# design.net
KiCad netlist of a schematic drawn in Altium Designer
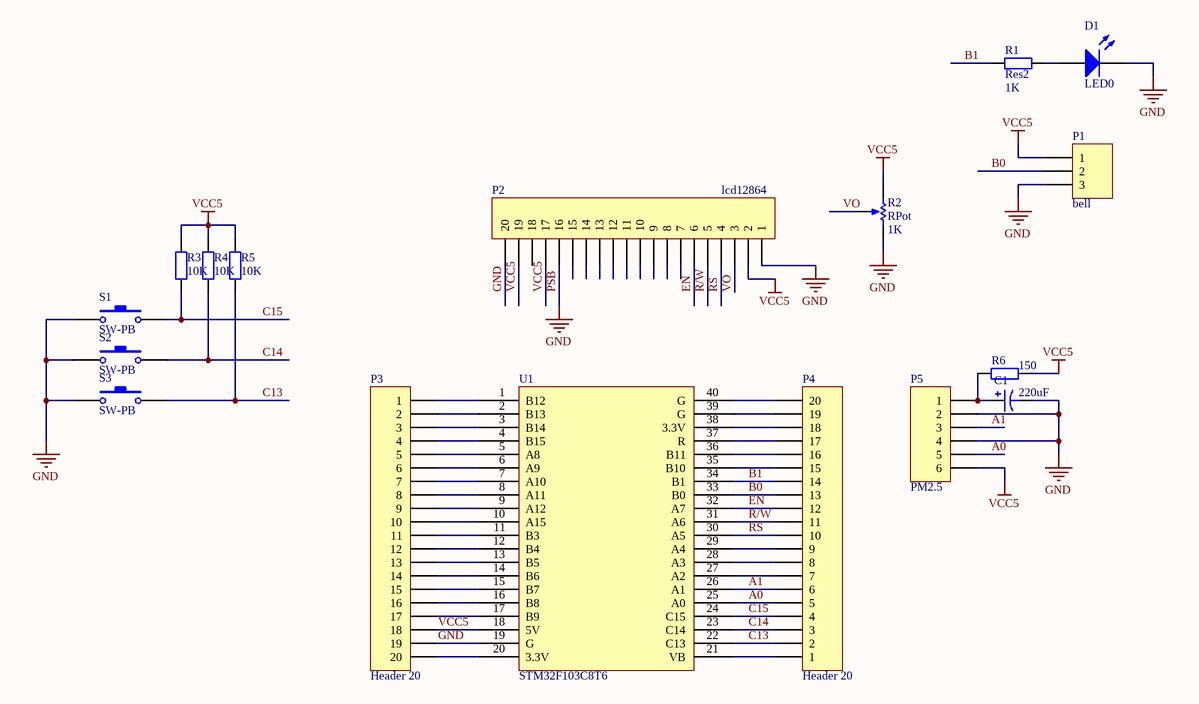
[diagram p0: 基于单片机的无线红外防盗报警系统原理图.SchDoc]

(export (version "E")
  (design (tool "Eeschema 10.0.6"))
  (components
    (comp (ref "C1")
      (value "220uF")
      (footprint "RB.1/.3A")
      (description "Polarized Capacitor (Radial)")
      (fields (field (name "Comment") "Cap Pol1") (field (name "PUBLISHER") "Altium Limited"))
      (libsource (lib "Miscellaneous Devices") (part "Cap Pol1"))
    )
    (comp (ref "D1")
      (value "LED0")
      (footprint "LED0.1")
      (description "Typical INFRARED GaAs LED")
      (fields (field (name "PUBLISHER") "Altium Limited"))
      (libsource (lib "Miscellaneous Devices") (part "LED0"))
    )
    (comp (ref "P1")
      (value "bell")
      (footprint "HDR1X3")
      (description "Header, 3-Pin")
      (fields (field (name "PUBLISHER") "Altium Limited"))
      (libsource (lib "Miscellaneous Connectors") (part "Header 3"))
    )
    (comp (ref "P2")
      (value "lcd12864")
      (footprint "HDR1X20")
      (description "Header, 20-Pin")
      (fields (field (name "PUBLISHER") "Altium Limited"))
      (libsource (lib "") (part "Header 20_2"))
    )
    (comp (ref "P3")
      (value "Header 20")
      (footprint "HDR1X20")
      (description "Header, 20-Pin")
      (fields (field (name "PUBLISHER") "Altium Limited"))
      (libsource (lib "Miscellaneous Connectors") (part "Header 20"))
    )
    (comp (ref "P4")
      (value "Header 20")
      (footprint "HDR1X20")
      (description "Header, 20-Pin")
      (fields (field (name "PUBLISHER") "Altium Limited"))
      (libsource (lib "") (part "Header 20_1"))
    )
    (comp (ref "P5")
      (value "PM2.5")
      (footprint "HDR1X6")
      (description "Header, 6-Pin")
      (fields (field (name "PUBLISHER") "Altium Limited"))
      (libsource (lib "Miscellaneous Connectors") (part "Header 6"))
    )
    (comp (ref "R1")
      (value "Res2")
      (footprint "0805")
      (description "Resistor")
      (fields (field (name "ALTIUM_VALUE") "1K") (field (name "PUBLISHER") "Altium Limited"))
      (libsource (lib "") (part "Res2_1"))
    )
    (comp (ref "R2")
      (value "RPot")
      (footprint "VR5")
      (description "Potentiometer")
      (fields (field (name "ALTIUM_VALUE") "1K") (field (name "PUBLISHER") "Altium Limited"))
      (libsource (lib "Miscellaneous Devices") (part "RPot"))
    )
    (comp (ref "R3")
      (value "10K")
      (footprint "LC-0805_R")
      (description "Resistor")
      (fields (field (name "Comment") "Res2") (field (name "PUBLISHER") "Altium Limited"))
      (libsource (lib "Miscellaneous Devices") (part "Res2"))
    )
    (comp (ref "R4")
      (value "10K")
      (footprint "LC-0805_R")
      (description "Resistor")
      (fields (field (name "Comment") "Res2") (field (name "PUBLISHER") "Altium Limited"))
      (libsource (lib "Miscellaneous Devices") (part "Res2"))
    )
    (comp (ref "R5")
      (value "10K")
      (footprint "LC-0805_R")
      (description "Resistor")
      (fields (field (name "Comment") "Res2") (field (name "PUBLISHER") "Altium Limited"))
      (libsource (lib "Miscellaneous Devices") (part "Res2"))
    )
    (comp (ref "R6")
      (value "150")
      (footprint "LC-0805_R")
      (description "Resistor")
      (fields (field (name "Comment") "Res2") (field (name "PUBLISHER") "Altium Limited"))
      (libsource (lib "") (part "Res2_1"))
    )
    (comp (ref "S1")
      (value "SW-PB")
      (footprint "SW-PB2")
      (description "Switch")
      (fields (field (name "PUBLISHER") "Altium Limited"))
      (libsource (lib "Miscellaneous Devices") (part "SW-PB"))
    )
    (comp (ref "S2")
      (value "SW-PB")
      (footprint "SW-PB2")
      (description "Switch")
      (fields (field (name "PUBLISHER") "Altium Limited"))
      (libsource (lib "Miscellaneous Devices") (part "SW-PB"))
    )
    (comp (ref "S3")
      (value "SW-PB")
      (footprint "SW-PB2")
      (description "Switch")
      (fields (field (name "PUBLISHER") "Altium Limited"))
      (libsource (lib "Miscellaneous Devices") (part "SW-PB"))
    )
    (comp (ref "U1")
      (value "STM32F103C8T6")
      (footprint "132")
      (libsource (lib "stm32f103c8t6最小系统板") (part "Component_1"))
    )
  )
  (nets
    (net (code "1") (name "/A0") (class "Default")
      (node (ref "P4") (pin "5") (pinfunction "5_5") (pintype "passive"))
      (node (ref "P5") (pin "5") (pinfunction "5_5") (pintype "passive"))
      (node (ref "U1") (pin "25") (pinfunction "A0_25") (pintype "passive"))
    )
    (net (code "2") (name "/A1") (class "Default")
      (node (ref "P4") (pin "6") (pinfunction "6_6") (pintype "passive"))
      (node (ref "P5") (pin "3") (pinfunction "3_3") (pintype "passive"))
      (node (ref "U1") (pin "26") (pinfunction "A1_26") (pintype "passive"))
    )
    (net (code "3") (name "/B0") (class "Default")
      (node (ref "P1") (pin "2") (pinfunction "2_2") (pintype "passive"))
      (node (ref "P4") (pin "13") (pinfunction "13_13") (pintype "passive"))
      (node (ref "U1") (pin "33") (pinfunction "B0_33") (pintype "passive"))
    )
    (net (code "4") (name "/B1") (class "Default")
      (node (ref "P4") (pin "14") (pinfunction "14_14") (pintype "passive"))
      (node (ref "R1") (pin "1") (pinfunction "1_1") (pintype "passive"))
      (node (ref "U1") (pin "34") (pinfunction "B1_34") (pintype "passive"))
    )
    (net (code "5") (name "/C13") (class "Default")
      (node (ref "P4") (pin "2") (pinfunction "2_2") (pintype "passive"))
      (node (ref "R5") (pin "1") (pinfunction "1_1") (pintype "passive"))
      (node (ref "S3") (pin "2") (pinfunction "2_2") (pintype "passive"))
      (node (ref "U1") (pin "22") (pinfunction "C13_22") (pintype "passive"))
    )
    (net (code "6") (name "/C14") (class "Default")
      (node (ref "P4") (pin "3") (pinfunction "3_3") (pintype "passive"))
      (node (ref "R4") (pin "1") (pinfunction "1_1") (pintype "passive"))
      (node (ref "S2") (pin "2") (pinfunction "2_2") (pintype "passive"))
      (node (ref "U1") (pin "23") (pinfunction "C14_23") (pintype "passive"))
    )
    (net (code "7") (name "/C15") (class "Default")
      (node (ref "P4") (pin "4") (pinfunction "4_4") (pintype "passive"))
      (node (ref "R3") (pin "1") (pinfunction "1_1") (pintype "passive"))
      (node (ref "S1") (pin "2") (pinfunction "2_2") (pintype "passive"))
      (node (ref "U1") (pin "24") (pinfunction "C15_24") (pintype "passive"))
    )
    (net (code "8") (name "/EN") (class "Default")
      (node (ref "P2") (pin "6") (pinfunction "6_6") (pintype "passive"))
      (node (ref "P4") (pin "12") (pinfunction "12_12") (pintype "passive"))
      (node (ref "U1") (pin "32") (pinfunction "A7_32") (pintype "passive"))
    )
    (net (code "9") (name "/RS") (class "Default")
      (node (ref "P2") (pin "4") (pinfunction "4_4") (pintype "passive"))
      (node (ref "P4") (pin "10") (pinfunction "10_10") (pintype "passive"))
      (node (ref "U1") (pin "30") (pinfunction "A5_30") (pintype "passive"))
    )
    (net (code "10") (name "/R{slash}W") (class "Default")
      (node (ref "P2") (pin "5") (pinfunction "5_5") (pintype "passive"))
      (node (ref "P4") (pin "11") (pinfunction "11_11") (pintype "passive"))
      (node (ref "U1") (pin "31") (pinfunction "A6_31") (pintype "passive"))
    )
    (net (code "11") (name "/VO") (class "Default")
      (node (ref "P2") (pin "3") (pinfunction "3_3") (pintype "passive"))
      (node (ref "R2") (pin "3") (pinfunction "TAP_3") (pintype "passive"))
    )
    (net (code "12") (name "GND") (class "Default")
      (node (ref "C1") (pin "2") (pinfunction "2_2") (pintype "passive"))
      (node (ref "D1") (pin "2") (pinfunction "K_2") (pintype "passive"))
      (node (ref "P1") (pin "3") (pinfunction "3_3") (pintype "passive"))
      (node (ref "P2") (pin "1") (pinfunction "1_1") (pintype "passive"))
      (node (ref "P2") (pin "16") (pinfunction "16_16") (pintype "passive"))
      (node (ref "P2") (pin "20") (pinfunction "20_20") (pintype "passive"))
      (node (ref "P3") (pin "19") (pinfunction "19_19") (pintype "passive"))
      (node (ref "P5") (pin "2") (pinfunction "2_2") (pintype "passive"))
      (node (ref "P5") (pin "4") (pinfunction "4_4") (pintype "passive"))
      (node (ref "R2") (pin "2") (pinfunction "BOT_2") (pintype "passive"))
      (node (ref "S1") (pin "1") (pinfunction "1_1") (pintype "passive"))
      (node (ref "S2") (pin "1") (pinfunction "1_1") (pintype "passive"))
      (node (ref "S3") (pin "1") (pinfunction "1_1") (pintype "passive"))
      (node (ref "U1") (pin "19") (pinfunction "G_19") (pintype "passive"))
    )
    (net (code "13") (name "Net-(C1-Pad1)") (class "Default")
      (node (ref "C1") (pin "1") (pinfunction "1_1") (pintype "passive"))
      (node (ref "P5") (pin "1") (pinfunction "1_1") (pintype "passive"))
      (node (ref "R6") (pin "1") (pinfunction "1_1") (pintype "passive"))
    )
    (net (code "14") (name "Net-(D1-A)") (class "Default")
      (node (ref "D1") (pin "1") (pinfunction "A_1") (pintype "passive"))
      (node (ref "R1") (pin "2") (pinfunction "2_2") (pintype "passive"))
    )
    (net (code "15") (name "Net-(P3-Pad20)") (class "Default")
      (node (ref "P3") (pin "20") (pinfunction "20_20") (pintype "passive"))
      (node (ref "U1") (pin "20") (pinfunction "3.3V_20") (pintype "passive"))
    )
    (net (code "16") (name "Net-(P4-Pad18)") (class "Default")
      (node (ref "P4") (pin "18") (pinfunction "18_18") (pintype "passive"))
      (node (ref "U1") (pin "38") (pinfunction "3.3V_38") (pintype "passive"))
    )
    (net (code "17") (name "Net-(P4-Pad19)") (class "Default")
      (node (ref "P4") (pin "19") (pinfunction "19_19") (pintype "passive"))
      (node (ref "U1") (pin "39") (pinfunction "G_39") (pintype "passive"))
    )
    (net (code "18") (name "Net-(P4-Pad20)") (class "Default")
      (node (ref "P4") (pin "20") (pinfunction "20_20") (pintype "passive"))
      (node (ref "U1") (pin "40") (pinfunction "G_40") (pintype "passive"))
    )
    (net (code "19") (name "Net-(U1-A2)") (class "Default")
      (node (ref "P4") (pin "7") (pinfunction "7_7") (pintype "passive"))
      (node (ref "U1") (pin "27") (pinfunction "A2_27") (pintype "passive"))
    )
    (net (code "20") (name "Net-(U1-A3)") (class "Default")
      (node (ref "P4") (pin "8") (pinfunction "8_8") (pintype "passive"))
      (node (ref "U1") (pin "28") (pinfunction "A3_28") (pintype "passive"))
    )
    (net (code "21") (name "Net-(U1-A4)") (class "Default")
      (node (ref "P4") (pin "9") (pinfunction "9_9") (pintype "passive"))
      (node (ref "U1") (pin "29") (pinfunction "A4_29") (pintype "passive"))
    )
    (net (code "22") (name "Net-(U1-A8)") (class "Default")
      (node (ref "P3") (pin "5") (pinfunction "5_5") (pintype "passive"))
      (node (ref "U1") (pin "5") (pinfunction "A8_5") (pintype "passive"))
    )
    (net (code "23") (name "Net-(U1-A9)") (class "Default")
      (node (ref "P3") (pin "6") (pinfunction "6_6") (pintype "passive"))
      (node (ref "U1") (pin "6") (pinfunction "A9_6") (pintype "passive"))
    )
    (net (code "24") (name "Net-(U1-A10)") (class "Default")
      (node (ref "P3") (pin "7") (pinfunction "7_7") (pintype "passive"))
      (node (ref "U1") (pin "7") (pinfunction "A10_7") (pintype "passive"))
    )
    (net (code "25") (name "Net-(U1-A11)") (class "Default")
      (node (ref "P3") (pin "8") (pinfunction "8_8") (pintype "passive"))
      (node (ref "U1") (pin "8") (pinfunction "A11_8") (pintype "passive"))
    )
    (net (code "26") (name "Net-(U1-A12)") (class "Default")
      (node (ref "P3") (pin "9") (pinfunction "9_9") (pintype "passive"))
      (node (ref "U1") (pin "9") (pinfunction "A12_9") (pintype "passive"))
    )
    (net (code "27") (name "Net-(U1-A15)") (class "Default")
      (node (ref "P3") (pin "10") (pinfunction "10_10") (pintype "passive"))
      (node (ref "U1") (pin "10") (pinfunction "A15_10") (pintype "passive"))
    )
    (net (code "28") (name "Net-(U1-B3)") (class "Default")
      (node (ref "P3") (pin "11") (pinfunction "11_11") (pintype "passive"))
      (node (ref "U1") (pin "11") (pinfunction "B3_11") (pintype "passive"))
    )
    (net (code "29") (name "Net-(U1-B4)") (class "Default")
      (node (ref "P3") (pin "12") (pinfunction "12_12") (pintype "passive"))
      (node (ref "U1") (pin "12") (pinfunction "B4_12") (pintype "passive"))
    )
    (net (code "30") (name "Net-(U1-B5)") (class "Default")
      (node (ref "P3") (pin "13") (pinfunction "13_13") (pintype "passive"))
      (node (ref "U1") (pin "13") (pinfunction "B5_13") (pintype "passive"))
    )
    (net (code "31") (name "Net-(U1-B6)") (class "Default")
      (node (ref "P3") (pin "14") (pinfunction "14_14") (pintype "passive"))
      (node (ref "U1") (pin "14") (pinfunction "B6_14") (pintype "passive"))
    )
    (net (code "32") (name "Net-(U1-B7)") (class "Default")
      (node (ref "P3") (pin "15") (pinfunction "15_15") (pintype "passive"))
      (node (ref "U1") (pin "15") (pinfunction "B7_15") (pintype "passive"))
    )
    (net (code "33") (name "Net-(U1-B8)") (class "Default")
      (node (ref "P3") (pin "16") (pinfunction "16_16") (pintype "passive"))
      (node (ref "U1") (pin "16") (pinfunction "B8_16") (pintype "passive"))
    )
    (net (code "34") (name "Net-(U1-B9)") (class "Default")
      (node (ref "P3") (pin "17") (pinfunction "17_17") (pintype "passive"))
      (node (ref "U1") (pin "17") (pinfunction "B9_17") (pintype "passive"))
    )
    (net (code "35") (name "Net-(U1-B10)") (class "Default")
      (node (ref "P4") (pin "15") (pinfunction "15_15") (pintype "passive"))
      (node (ref "U1") (pin "35") (pinfunction "B10_35") (pintype "passive"))
    )
    (net (code "36") (name "Net-(U1-B11)") (class "Default")
      (node (ref "P4") (pin "16") (pinfunction "16_16") (pintype "passive"))
      (node (ref "U1") (pin "36") (pinfunction "B11_36") (pintype "passive"))
    )
    (net (code "37") (name "Net-(U1-B12)") (class "Default")
      (node (ref "P3") (pin "1") (pinfunction "1_1") (pintype "passive"))
      (node (ref "U1") (pin "1") (pinfunction "B12_1") (pintype "passive"))
    )
    (net (code "38") (name "Net-(U1-B13)") (class "Default")
      (node (ref "P3") (pin "2") (pinfunction "2_2") (pintype "passive"))
      (node (ref "U1") (pin "2") (pinfunction "B13_2") (pintype "passive"))
    )
    (net (code "39") (name "Net-(U1-B14)") (class "Default")
      (node (ref "P3") (pin "3") (pinfunction "3_3") (pintype "passive"))
      (node (ref "U1") (pin "3") (pinfunction "B14_3") (pintype "passive"))
    )
    (net (code "40") (name "Net-(U1-B15)") (class "Default")
      (node (ref "P3") (pin "4") (pinfunction "4_4") (pintype "passive"))
      (node (ref "U1") (pin "4") (pinfunction "B15_4") (pintype "passive"))
    )
    (net (code "41") (name "Net-(U1-R)") (class "Default")
      (node (ref "P4") (pin "17") (pinfunction "17_17") (pintype "passive"))
      (node (ref "U1") (pin "37") (pinfunction "R_37") (pintype "passive"))
    )
    (net (code "42") (name "Net-(U1-VB)") (class "Default")
      (node (ref "P4") (pin "1") (pinfunction "1_1") (pintype "passive"))
      (node (ref "U1") (pin "21") (pinfunction "VB_21") (pintype "passive"))
    )
    (net (code "43") (name "VCC5") (class "Default")
      (node (ref "P1") (pin "1") (pinfunction "1_1") (pintype "passive"))
      (node (ref "P2") (pin "17") (pinfunction "17_17") (pintype "passive"))
      (node (ref "P2") (pin "19") (pinfunction "19_19") (pintype "passive"))
      (node (ref "P2") (pin "2") (pinfunction "2_2") (pintype "passive"))
      (node (ref "P3") (pin "18") (pinfunction "18_18") (pintype "passive"))
      (node (ref "P5") (pin "6") (pinfunction "6_6") (pintype "passive"))
      (node (ref "R2") (pin "1") (pinfunction "TOP_1") (pintype "passive"))
      (node (ref "R3") (pin "2") (pinfunction "2_2") (pintype "passive"))
      (node (ref "R4") (pin "2") (pinfunction "2_2") (pintype "passive"))
      (node (ref "R5") (pin "2") (pinfunction "2_2") (pintype "passive"))
      (node (ref "R6") (pin "2") (pinfunction "2_2") (pintype "passive"))
      (node (ref "U1") (pin "18") (pinfunction "5V_18") (pintype "passive"))
    )
    (net (code "44") (name "unconnected-(P2-Pad7)") (class "Default")
      (node (ref "P2") (pin "7") (pinfunction "7_7") (pintype "passive"))
    )
    (net (code "45") (name "unconnected-(P2-Pad8)") (class "Default")
      (node (ref "P2") (pin "8") (pinfunction "8_8") (pintype "passive"))
    )
    (net (code "46") (name "unconnected-(P2-Pad9)") (class "Default")
      (node (ref "P2") (pin "9") (pinfunction "9_9") (pintype "passive"))
    )
    (net (code "47") (name "unconnected-(P2-Pad10)") (class "Default")
      (node (ref "P2") (pin "10") (pinfunction "10_10") (pintype "passive"))
    )
    (net (code "48") (name "unconnected-(P2-Pad11)") (class "Default")
      (node (ref "P2") (pin "11") (pinfunction "11_11") (pintype "passive"))
    )
    (net (code "49") (name "unconnected-(P2-Pad12)") (class "Default")
      (node (ref "P2") (pin "12") (pinfunction "12_12") (pintype "passive"))
    )
    (net (code "50") (name "unconnected-(P2-Pad13)") (class "Default")
      (node (ref "P2") (pin "13") (pinfunction "13_13") (pintype "passive"))
    )
    (net (code "51") (name "unconnected-(P2-Pad14)") (class "Default")
      (node (ref "P2") (pin "14") (pinfunction "14_14") (pintype "passive"))
    )
    (net (code "52") (name "unconnected-(P2-Pad15)") (class "Default")
      (node (ref "P2") (pin "15") (pinfunction "15_15") (pintype "passive"))
    )
    (net (code "53") (name "unconnected-(P2-Pad18)") (class "Default")
      (node (ref "P2") (pin "18") (pinfunction "18_18") (pintype "passive"))
    )
  )
)
